# lamp7.net
KiCad netlist of a schematic drawn in EAGLE
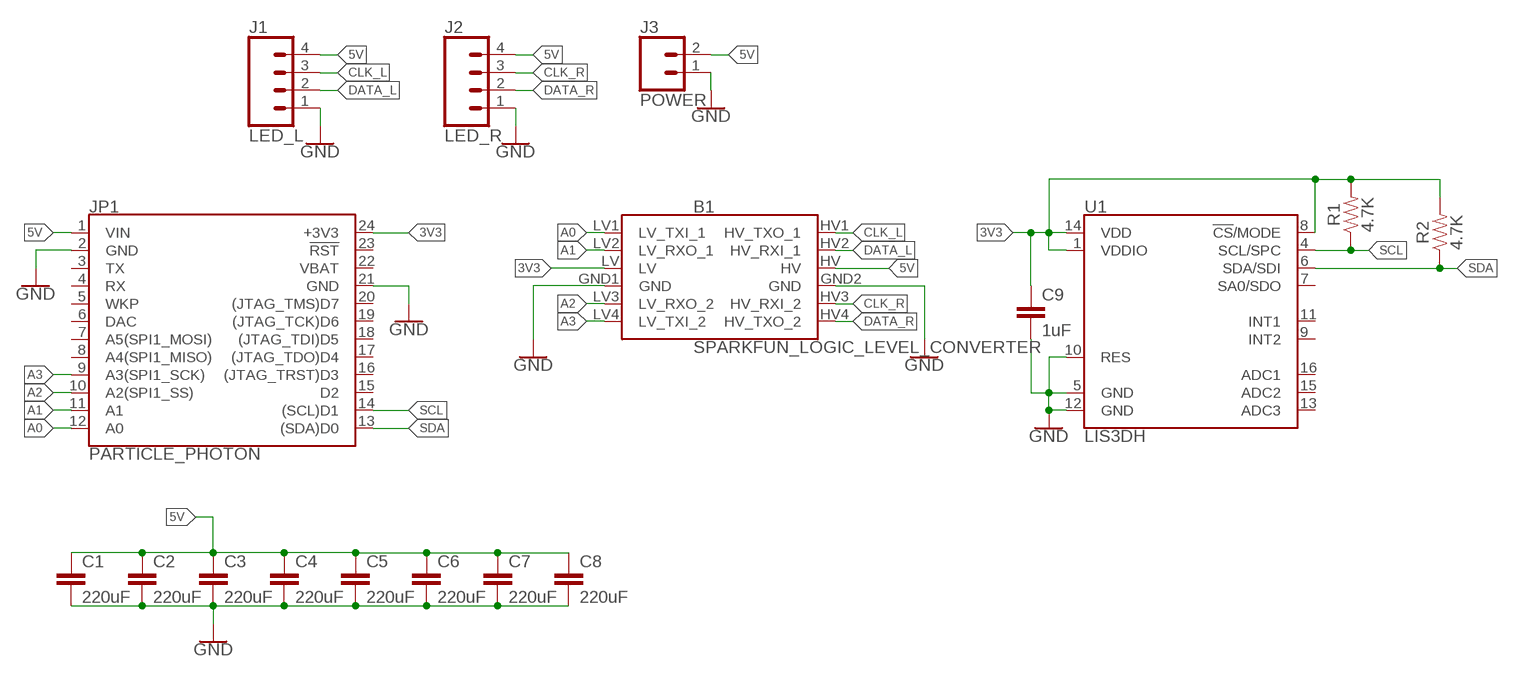
[diagram p0: schematic, sheet 1]

(export (version "E")
  (design (tool "Eeschema 10.0.6"))
  (components
    (comp (ref "B1")
      (value "SPARKFUN_LOGIC_LEVEL_CONVERTER")
      (footprint "eagle-import:SPARKFUN_LOGIC_LEVEL_CONVERTER")
      (libsource (lib "eagle-import") (part "SPARKFUN_LOGIC_LEVEL_CONVERTER"))
    )
    (comp (ref "C1")
      (value "220uF")
      (footprint "eagle-import:1206")
      (libsource (lib "eagle-import") (part "2.2UF-1206-50V-10%"))
    )
    (comp (ref "C2")
      (value "220uF")
      (footprint "eagle-import:1206")
      (libsource (lib "eagle-import") (part "2.2UF-1206-50V-10%"))
    )
    (comp (ref "C3")
      (value "220uF")
      (footprint "eagle-import:1206")
      (libsource (lib "eagle-import") (part "2.2UF-1206-50V-10%"))
    )
    (comp (ref "C4")
      (value "220uF")
      (footprint "eagle-import:1206")
      (libsource (lib "eagle-import") (part "2.2UF-1206-50V-10%"))
    )
    (comp (ref "C5")
      (value "220uF")
      (footprint "eagle-import:1206")
      (libsource (lib "eagle-import") (part "2.2UF-1206-50V-10%"))
    )
    (comp (ref "C6")
      (value "220uF")
      (footprint "eagle-import:1206")
      (libsource (lib "eagle-import") (part "2.2UF-1206-50V-10%"))
    )
    (comp (ref "C7")
      (value "220uF")
      (footprint "eagle-import:1206")
      (libsource (lib "eagle-import") (part "2.2UF-1206-50V-10%"))
    )
    (comp (ref "C8")
      (value "220uF")
      (footprint "eagle-import:1206")
      (libsource (lib "eagle-import") (part "2.2UF-1206-50V-10%"))
    )
    (comp (ref "C9")
      (value "1uF")
      (footprint "eagle-import:0603")
      (libsource (lib "eagle-import") (part "0.1UF-0603-25V-(+80/-20%)"))
    )
    (comp (ref "J1")
      (value "LED_L")
      (footprint "eagle-import:1X04_LONGPADS")
      (libsource (lib "eagle-import") (part "CONN_04LONGPADS"))
    )
    (comp (ref "J2")
      (value "LED_R")
      (footprint "eagle-import:1X04_LONGPADS")
      (libsource (lib "eagle-import") (part "CONN_04LONGPADS"))
    )
    (comp (ref "J3")
      (value "POWER")
      (footprint "eagle-import:1X02_LOCK_LONGPADS")
      (libsource (lib "eagle-import") (part "CONN_02LOCK_LONGPADS"))
    )
    (comp (ref "JP1")
      (value "PARTICLE_PHOTON")
      (footprint "eagle-import:PARTICLE_PHOTON")
      (libsource (lib "eagle-import") (part "PARTICLE_PHOTON"))
    )
    (comp (ref "R1")
      (value "4.7K")
      (footprint "eagle-import:0603")
      (libsource (lib "eagle-import") (part "0OHM-0603-1/10W-5%"))
    )
    (comp (ref "R2")
      (value "4.7K")
      (footprint "eagle-import:0603")
      (libsource (lib "eagle-import") (part "0OHM-0603-1/10W-5%"))
    )
    (comp (ref "U1")
      (value "LIS3DH")
      (footprint "eagle-import:LGA-16-3X3")
      (libsource (lib "eagle-import") (part "LIS3DH"))
    )
  )
  (nets
    (net (code "1") (name "/VBAT") (class "Default")
      (node (ref "JP1") (pin "22") (pinfunction "VBAT_22") (pintype "power_in"))
    )
    (net (code "2") (name "3V3") (class "Default")
      (node (ref "B1") (pin "LV") (pinfunction "LV_LV") (pintype "power_in"))
      (node (ref "C9") (pin "1") (pinfunction "1_1") (pintype "passive"))
      (node (ref "JP1") (pin "24") (pinfunction "+3V3_24") (pintype "power_in"))
      (node (ref "R1") (pin "2") (pinfunction "2_2") (pintype "passive"))
      (node (ref "R2") (pin "2") (pinfunction "2_2") (pintype "passive"))
      (node (ref "U1") (pin "1") (pinfunction "VDDIO_1") (pintype "bidirectional"))
      (node (ref "U1") (pin "14") (pinfunction "VDD_14") (pintype "bidirectional"))
      (node (ref "U1") (pin "8") (pinfunction "~{CS}/MODE_8") (pintype "bidirectional"))
    )
    (net (code "3") (name "5V") (class "Default")
      (node (ref "B1") (pin "HV") (pinfunction "HV_HV") (pintype "power_in"))
      (node (ref "C1") (pin "1") (pinfunction "1_1") (pintype "passive"))
      (node (ref "C2") (pin "1") (pinfunction "1_1") (pintype "passive"))
      (node (ref "C3") (pin "1") (pinfunction "1_1") (pintype "passive"))
      (node (ref "C4") (pin "1") (pinfunction "1_1") (pintype "passive"))
      (node (ref "C5") (pin "1") (pinfunction "1_1") (pintype "passive"))
      (node (ref "C6") (pin "1") (pinfunction "1_1") (pintype "passive"))
      (node (ref "C7") (pin "1") (pinfunction "1_1") (pintype "passive"))
      (node (ref "C8") (pin "1") (pinfunction "1_1") (pintype "passive"))
      (node (ref "J1") (pin "4") (pinfunction "4_4") (pintype "passive"))
      (node (ref "J2") (pin "4") (pinfunction "4_4") (pintype "passive"))
      (node (ref "J3") (pin "2") (pinfunction "2_2") (pintype "passive"))
      (node (ref "JP1") (pin "1") (pinfunction "VIN_1") (pintype "power_in"))
    )
    (net (code "4") (name "A0") (class "Default")
      (node (ref "B1") (pin "LV1") (pinfunction "LV_TXI_1_LV1") (pintype "bidirectional"))
      (node (ref "JP1") (pin "12") (pinfunction "A0_12") (pintype "bidirectional"))
    )
    (net (code "5") (name "A1") (class "Default")
      (node (ref "B1") (pin "LV2") (pinfunction "LV_RXO_1_LV2") (pintype "bidirectional"))
      (node (ref "JP1") (pin "11") (pinfunction "A1_11") (pintype "bidirectional"))
    )
    (net (code "6") (name "A2") (class "Default")
      (node (ref "B1") (pin "LV3") (pinfunction "LV_RXO_2_LV3") (pintype "bidirectional"))
      (node (ref "JP1") (pin "10") (pinfunction "A2(SPI1_SS)_10") (pintype "bidirectional"))
    )
    (net (code "7") (name "A3") (class "Default")
      (node (ref "B1") (pin "LV4") (pinfunction "LV_TXI_2_LV4") (pintype "bidirectional"))
      (node (ref "JP1") (pin "9") (pinfunction "A3(SPI1_SCK)_9") (pintype "bidirectional"))
    )
    (net (code "8") (name "CLK_L") (class "Default")
      (node (ref "B1") (pin "HV1") (pinfunction "HV_TXO_1_HV1") (pintype "bidirectional"))
      (node (ref "J1") (pin "3") (pinfunction "3_3") (pintype "passive"))
    )
    (net (code "9") (name "CLK_R") (class "Default")
      (node (ref "B1") (pin "HV3") (pinfunction "HV_RXI_2_HV3") (pintype "bidirectional"))
      (node (ref "J2") (pin "3") (pinfunction "3_3") (pintype "passive"))
    )
    (net (code "10") (name "DATA_L") (class "Default")
      (node (ref "B1") (pin "HV2") (pinfunction "HV_RXI_1_HV2") (pintype "bidirectional"))
      (node (ref "J1") (pin "2") (pinfunction "2_2") (pintype "passive"))
    )
    (net (code "11") (name "DATA_R") (class "Default")
      (node (ref "B1") (pin "HV4") (pinfunction "HV_TXO_2_HV4") (pintype "bidirectional"))
      (node (ref "J2") (pin "2") (pinfunction "2_2") (pintype "passive"))
    )
    (net (code "12") (name "GND") (class "Default")
      (node (ref "B1") (pin "GND1") (pinfunction "GND_GND1") (pintype "power_in"))
      (node (ref "B1") (pin "GND2") (pinfunction "GND_GND2") (pintype "power_in"))
      (node (ref "C1") (pin "2") (pinfunction "2_2") (pintype "passive"))
      (node (ref "C2") (pin "2") (pinfunction "2_2") (pintype "passive"))
      (node (ref "C3") (pin "2") (pinfunction "2_2") (pintype "passive"))
      (node (ref "C4") (pin "2") (pinfunction "2_2") (pintype "passive"))
      (node (ref "C5") (pin "2") (pinfunction "2_2") (pintype "passive"))
      (node (ref "C6") (pin "2") (pinfunction "2_2") (pintype "passive"))
      (node (ref "C7") (pin "2") (pinfunction "2_2") (pintype "passive"))
      (node (ref "C8") (pin "2") (pinfunction "2_2") (pintype "passive"))
      (node (ref "C9") (pin "2") (pinfunction "2_2") (pintype "passive"))
      (node (ref "J1") (pin "1") (pinfunction "1_1") (pintype "passive"))
      (node (ref "J2") (pin "1") (pinfunction "1_1") (pintype "passive"))
      (node (ref "J3") (pin "1") (pinfunction "1_1") (pintype "passive"))
      (node (ref "JP1") (pin "2") (pinfunction "GND_2") (pintype "power_in"))
      (node (ref "JP1") (pin "21") (pinfunction "GND_21") (pintype "power_in"))
      (node (ref "U1") (pin "10") (pinfunction "RES_10") (pintype "bidirectional"))
      (node (ref "U1") (pin "12") (pinfunction "GND_12") (pintype "bidirectional"))
      (node (ref "U1") (pin "5") (pinfunction "GND_5") (pintype "bidirectional"))
    )
    (net (code "13") (name "SCL") (class "Default")
      (node (ref "JP1") (pin "14") (pinfunction "(SCL)D1_14") (pintype "bidirectional"))
      (node (ref "R1") (pin "1") (pinfunction "1_1") (pintype "passive"))
      (node (ref "U1") (pin "4") (pinfunction "SCL/SPC_4") (pintype "bidirectional"))
    )
    (net (code "14") (name "SDA") (class "Default")
      (node (ref "JP1") (pin "13") (pinfunction "(SDA)D0_13") (pintype "bidirectional"))
      (node (ref "R2") (pin "1") (pinfunction "1_1") (pintype "passive"))
      (node (ref "U1") (pin "6") (pinfunction "SDA/SDI_6") (pintype "bidirectional"))
    )
    (net (code "15") (name "unconnected-(JP1-(JTAG_TCK)D6-Pad19)") (class "Default")
      (node (ref "JP1") (pin "19") (pinfunction "(JTAG_TCK)D6_19") (pintype "bidirectional"))
    )
    (net (code "16") (name "unconnected-(JP1-(JTAG_TDI)D5-Pad18)") (class "Default")
      (node (ref "JP1") (pin "18") (pinfunction "(JTAG_TDI)D5_18") (pintype "bidirectional"))
    )
    (net (code "17") (name "unconnected-(JP1-(JTAG_TDO)D4-Pad17)") (class "Default")
      (node (ref "JP1") (pin "17") (pinfunction "(JTAG_TDO)D4_17") (pintype "bidirectional"))
    )
    (net (code "18") (name "unconnected-(JP1-(JTAG_TMS)D7-Pad20)") (class "Default")
      (node (ref "JP1") (pin "20") (pinfunction "(JTAG_TMS)D7_20") (pintype "bidirectional"))
    )
    (net (code "19") (name "unconnected-(JP1-(JTAG_TRST)D3-Pad16)") (class "Default")
      (node (ref "JP1") (pin "16") (pinfunction "(JTAG_TRST)D3_16") (pintype "bidirectional"))
    )
    (net (code "20") (name "unconnected-(JP1-A4(SPI1_MISO)-Pad8)") (class "Default")
      (node (ref "JP1") (pin "8") (pinfunction "A4(SPI1_MISO)_8") (pintype "bidirectional"))
    )
    (net (code "21") (name "unconnected-(JP1-A5(SPI1_MOSI)-Pad7)") (class "Default")
      (node (ref "JP1") (pin "7") (pinfunction "A5(SPI1_MOSI)_7") (pintype "bidirectional"))
    )
    (net (code "22") (name "unconnected-(JP1-D2-Pad15)") (class "Default")
      (node (ref "JP1") (pin "15") (pinfunction "D2_15") (pintype "bidirectional"))
    )
    (net (code "23") (name "unconnected-(JP1-DAC-Pad6)") (class "Default")
      (node (ref "JP1") (pin "6") (pinfunction "DAC_6") (pintype "bidirectional"))
    )
    (net (code "24") (name "unconnected-(JP1-RX-Pad4)") (class "Default")
      (node (ref "JP1") (pin "4") (pinfunction "RX_4") (pintype "bidirectional"))
    )
    (net (code "25") (name "unconnected-(JP1-TX-Pad3)") (class "Default")
      (node (ref "JP1") (pin "3") (pinfunction "TX_3") (pintype "bidirectional"))
    )
    (net (code "26") (name "unconnected-(JP1-WKP-Pad5)") (class "Default")
      (node (ref "JP1") (pin "5") (pinfunction "WKP_5") (pintype "bidirectional"))
    )
    (net (code "27") (name "unconnected-(JP1-~{RST}-Pad23)") (class "Default")
      (node (ref "JP1") (pin "23") (pinfunction "~{RST}_23") (pintype "bidirectional"))
    )
    (net (code "28") (name "unconnected-(U1-ADC1-Pad16)") (class "Default")
      (node (ref "U1") (pin "16") (pinfunction "ADC1_16") (pintype "bidirectional"))
    )
    (net (code "29") (name "unconnected-(U1-ADC2-Pad15)") (class "Default")
      (node (ref "U1") (pin "15") (pinfunction "ADC2_15") (pintype "bidirectional"))
    )
    (net (code "30") (name "unconnected-(U1-ADC3-Pad13)") (class "Default")
      (node (ref "U1") (pin "13") (pinfunction "ADC3_13") (pintype "bidirectional"))
    )
    (net (code "31") (name "unconnected-(U1-INT1-Pad11)") (class "Default")
      (node (ref "U1") (pin "11") (pinfunction "INT1_11") (pintype "bidirectional"))
    )
    (net (code "32") (name "unconnected-(U1-INT2-Pad9)") (class "Default")
      (node (ref "U1") (pin "9") (pinfunction "INT2_9") (pintype "bidirectional"))
    )
    (net (code "33") (name "unconnected-(U1-SA0{slash}SDO-Pad7)") (class "Default")
      (node (ref "U1") (pin "7") (pinfunction "SA0/SDO_7") (pintype "bidirectional"))
    )
  )
)
